# opa.net
KiCad netlist of a schematic drawn in Altium Designer
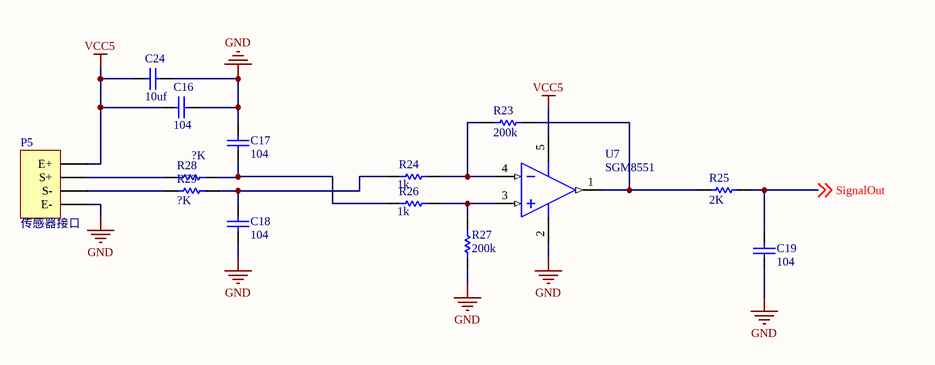
[diagram p0: opa.SchDoc]

(export (version "E")
  (design (tool "Eeschema 10.0.6"))
  (components
    (comp (ref "C16")
      (value "104")
      (footprint "C0805")
      (description "Capacitor")
      (fields (field (name "Comment") "Cap") (field (name "PUBLISHER") "Altium Limited"))
      (libsource (lib "Miscellaneous Devices") (part "Cap"))
    )
    (comp (ref "C17")
      (value "104")
      (footprint "C0805")
      (description "Capacitor")
      (fields (field (name "Comment") "Cap") (field (name "PUBLISHER") "Altium Limited"))
      (libsource (lib "Miscellaneous Devices") (part "Cap"))
    )
    (comp (ref "C18")
      (value "104")
      (footprint "C0805")
      (description "Capacitor")
      (fields (field (name "Comment") "Cap") (field (name "PUBLISHER") "Altium Limited"))
      (libsource (lib "Miscellaneous Devices") (part "Cap"))
    )
    (comp (ref "C19")
      (value "104")
      (footprint "C0805")
      (description "Capacitor")
      (fields (field (name "Comment") "Cap") (field (name "PUBLISHER") "Altium Limited"))
      (libsource (lib "Miscellaneous Devices") (part "Cap"))
    )
    (comp (ref "C24")
      (value "10uf")
      (footprint "C0805")
      (description "Capacitor")
      (fields (field (name "Comment") "Cap") (field (name "PUBLISHER") "Altium Limited"))
      (libsource (lib "Miscellaneous Devices") (part "Cap"))
    )
    (comp (ref "P5")
      (value "传感器接口")
      (footprint "HDR1X4")
      (description "Header, 4-Pin")
      (fields (field (name "PUBLISHER") "Altium Limited"))
      (libsource (lib "Miscellaneous Connectors") (part "Header 4"))
    )
    (comp (ref "R23")
      (value "200k")
      (footprint "6-0805_N")
      (description "Resistor")
      (fields (field (name "Comment") "Res1") (field (name "PUBLISHER") "Altium Limited"))
      (libsource (lib "Miscellaneous Devices") (part "Res1"))
    )
    (comp (ref "R24")
      (value "1k")
      (footprint "6-0805_N")
      (description "Resistor")
      (fields (field (name "Comment") "Res1") (field (name "PUBLISHER") "Altium Limited"))
      (libsource (lib "Miscellaneous Devices") (part "Res1"))
    )
    (comp (ref "R25")
      (value "2K")
      (footprint "6-0805_N")
      (description "Resistor")
      (fields (field (name "Comment") "Res1") (field (name "PUBLISHER") "Altium Limited"))
      (libsource (lib "Miscellaneous Devices") (part "Res1"))
    )
    (comp (ref "R26")
      (value "1k")
      (footprint "6-0805_N")
      (description "Resistor")
      (fields (field (name "Comment") "Res1") (field (name "PUBLISHER") "Altium Limited"))
      (libsource (lib "Miscellaneous Devices") (part "Res1"))
    )
    (comp (ref "R27")
      (value "200k")
      (footprint "6-0805_N")
      (description "Resistor")
      (fields (field (name "Comment") "Res1") (field (name "PUBLISHER") "Altium Limited"))
      (libsource (lib "Miscellaneous Devices") (part "Res1"))
    )
    (comp (ref "R28")
      (value "?K")
      (footprint "6-0805_N")
      (description "Resistor")
      (fields (field (name "Comment") "Res1") (field (name "PUBLISHER") "Altium Limited"))
      (libsource (lib "Miscellaneous Devices") (part "Res1"))
    )
    (comp (ref "R29")
      (value "?K")
      (footprint "6-0805_N")
      (description "Resistor")
      (fields (field (name "Comment") "Res1") (field (name "PUBLISHER") "Altium Limited"))
      (libsource (lib "Miscellaneous Devices") (part "Res1"))
    )
    (comp (ref "U7")
      (value "SGM8551")
      (footprint "SOT23-5_N")
      (description "High-Speed, Single-Supply, Gain of +2, Closed-Loop, Rail-to-Rail Buffer with Enable")
      (fields (field (name "PUBLISHER") "Altium Limited"))
      (libsource (lib "Maxim Amplifier Buffer") (part "MAX4214EUK-T"))
    )
  )
  (nets
    (net (code "1") (name "GND") (class "Default")
      (node (ref "C16") (pin "1") (pinfunction "1_1") (pintype "passive"))
      (node (ref "C17") (pin "2") (pinfunction "2_2") (pintype "passive"))
      (node (ref "C18") (pin "1") (pinfunction "1_1") (pintype "passive"))
      (node (ref "C19") (pin "1") (pinfunction "1_1") (pintype "passive"))
      (node (ref "C24") (pin "1") (pinfunction "1_1") (pintype "passive"))
      (node (ref "P5") (pin "4") (pinfunction "E-_4") (pintype "passive"))
      (node (ref "R27") (pin "1") (pinfunction "1_1") (pintype "passive"))
      (node (ref "U7") (pin "2") (pinfunction "VEE_2") (pintype "power_in"))
    )
    (net (code "2") (name "Net-(C17-Pad1)") (class "Default")
      (node (ref "C17") (pin "1") (pinfunction "1_1") (pintype "passive"))
      (node (ref "R26") (pin "1") (pinfunction "1_1") (pintype "passive"))
      (node (ref "R28") (pin "1") (pinfunction "1_1") (pintype "passive"))
    )
    (net (code "3") (name "Net-(C18-Pad2)") (class "Default")
      (node (ref "C18") (pin "2") (pinfunction "2_2") (pintype "passive"))
      (node (ref "R24") (pin "1") (pinfunction "1_1") (pintype "passive"))
      (node (ref "R29") (pin "1") (pinfunction "1_1") (pintype "passive"))
    )
    (net (code "4") (name "Net-(P5-S+)") (class "Default")
      (node (ref "P5") (pin "2") (pinfunction "S+_2") (pintype "passive"))
      (node (ref "R28") (pin "2") (pinfunction "2_2") (pintype "passive"))
    )
    (net (code "5") (name "Net-(P5-S-)") (class "Default")
      (node (ref "P5") (pin "3") (pinfunction "S-_3") (pintype "passive"))
      (node (ref "R29") (pin "2") (pinfunction "2_2") (pintype "passive"))
    )
    (net (code "6") (name "Net-(U7-IN+)") (class "Default")
      (node (ref "R26") (pin "2") (pinfunction "2_2") (pintype "passive"))
      (node (ref "R27") (pin "2") (pinfunction "2_2") (pintype "passive"))
      (node (ref "U7") (pin "3") (pinfunction "IN+_3") (pintype "input"))
    )
    (net (code "7") (name "Net-(U7-IN-)") (class "Default")
      (node (ref "R23") (pin "2") (pinfunction "2_2") (pintype "passive"))
      (node (ref "R24") (pin "2") (pinfunction "2_2") (pintype "passive"))
      (node (ref "U7") (pin "4") (pinfunction "IN-_4") (pintype "input"))
    )
    (net (code "8") (name "Net-(U7-OUT)") (class "Default")
      (node (ref "R23") (pin "1") (pinfunction "1_1") (pintype "passive"))
      (node (ref "R25") (pin "2") (pinfunction "2_2") (pintype "passive"))
      (node (ref "U7") (pin "1") (pinfunction "OUT_1") (pintype "output"))
    )
    (net (code "9") (name "SignalOut") (class "Default")
      (node (ref "C19") (pin "2") (pinfunction "2_2") (pintype "passive"))
      (node (ref "R25") (pin "1") (pinfunction "1_1") (pintype "passive"))
    )
    (net (code "10") (name "VCC5") (class "Default")
      (node (ref "C16") (pin "2") (pinfunction "2_2") (pintype "passive"))
      (node (ref "C24") (pin "2") (pinfunction "2_2") (pintype "passive"))
      (node (ref "P5") (pin "1") (pinfunction "E+_1") (pintype "passive"))
      (node (ref "U7") (pin "5") (pinfunction "VCC_5") (pintype "power_in"))
    )
  )
)
